# SCH_ocula-mux-bridge-1_1.net
KiCad netlist of a schematic drawn in EasyEDA
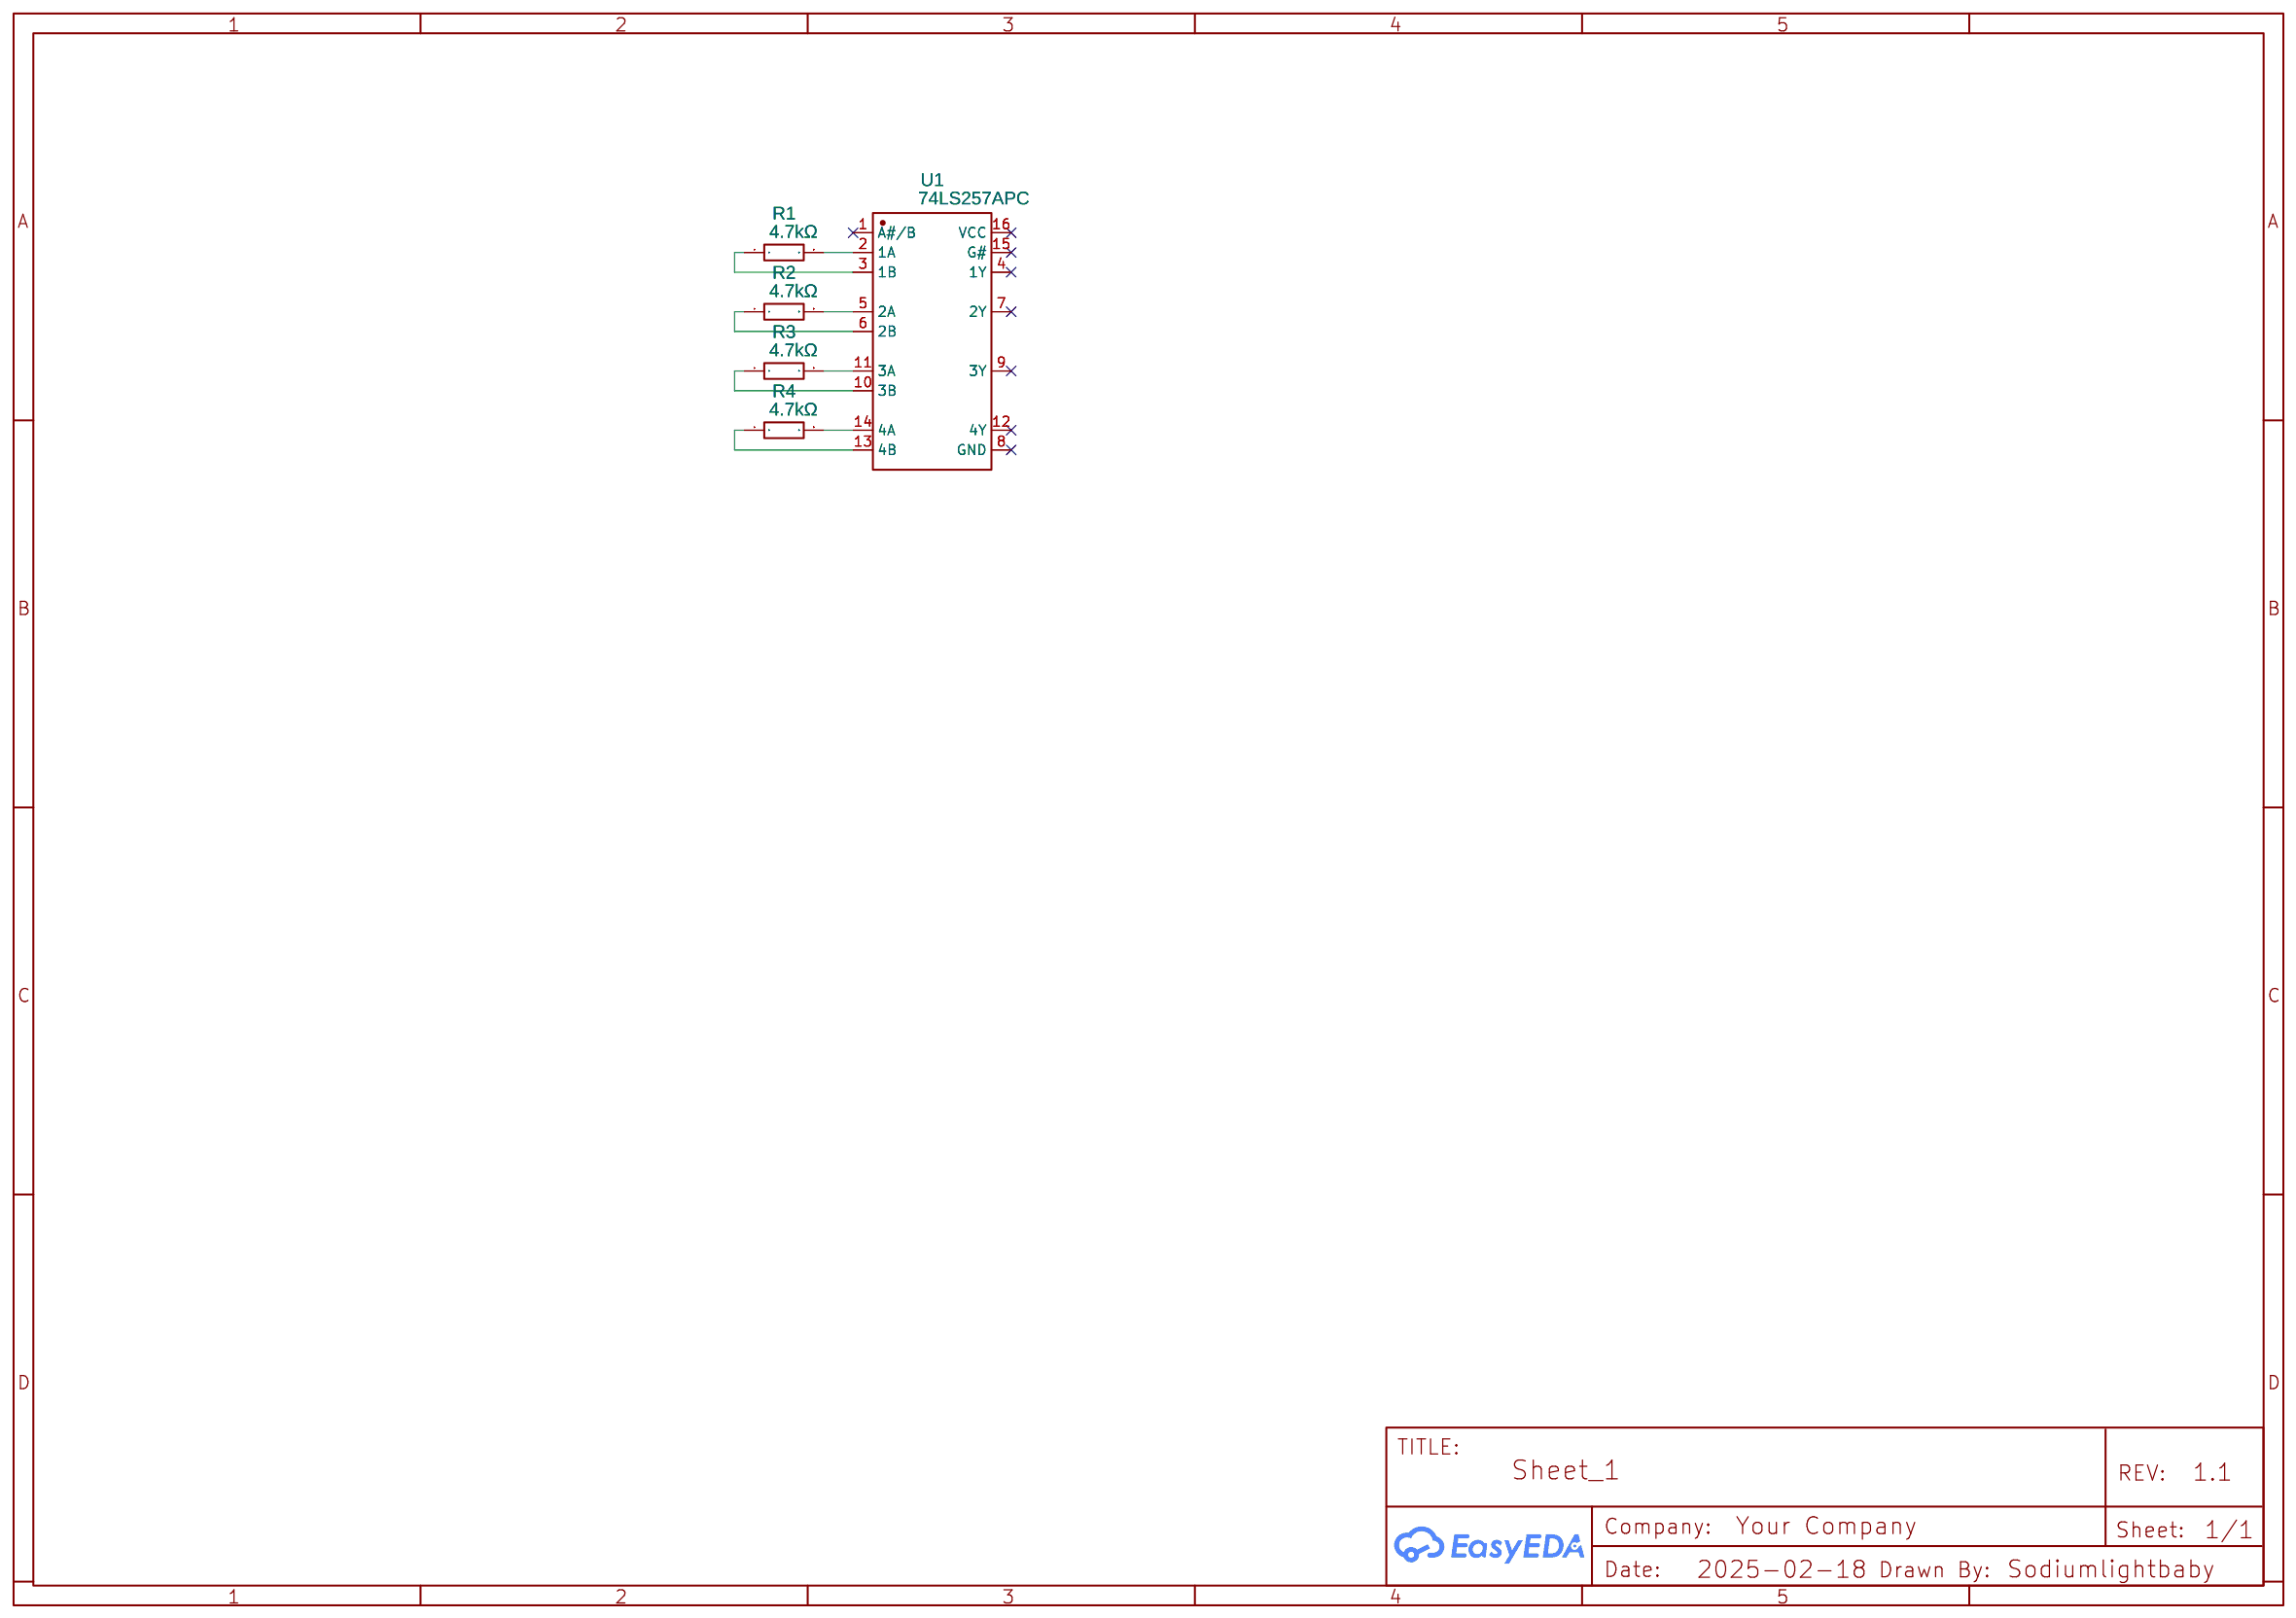
[diagram p0: schematic sheet]

(export (version "E")
  (design (tool "Eeschema 10.0.6"))
  (components
    (comp (ref "R1")
      (value "4.7kΩ")
      (fields
        (field (name "Manufacturer Part") "0805W8F4701T5E")
        (field (name "Manufacturer") "UNI-ROYAL(厚声)")
      )
      (libsource (lib "") (part "0805W8F4701T5E"))
    )
    (comp (ref "R2")
      (value "4.7kΩ")
      (fields
        (field (name "Manufacturer Part") "0805W8F4701T5E")
        (field (name "Manufacturer") "UNI-ROYAL(厚声)")
      )
      (libsource (lib "") (part "0805W8F4701T5E"))
    )
    (comp (ref "R3")
      (value "4.7kΩ")
      (fields
        (field (name "Manufacturer Part") "0805W8F4701T5E")
        (field (name "Manufacturer") "UNI-ROYAL(厚声)")
      )
      (libsource (lib "") (part "0805W8F4701T5E"))
    )
    (comp (ref "R4")
      (value "4.7kΩ")
      (fields
        (field (name "Manufacturer Part") "0805W8F4701T5E")
        (field (name "Manufacturer") "UNI-ROYAL(厚声)")
      )
      (libsource (lib "") (part "0805W8F4701T5E"))
    )
    (comp (ref "U1")
      (value "74LS257APC")
      (fields (field (name "Manufacturer") "TI(德州仪器)"))
      (libsource (lib "") (part "74LS257APC"))
    )
  )
  (nets
    (net (code "1") (name "Net-(U1-1A)") (class "Default")
      (node (ref "R1") (pin "2") (pinfunction "2_2") (pintype "input"))
      (node (ref "U1") (pin "2") (pinfunction "1A_2") (pintype "unspecified"))
    )
    (net (code "2") (name "Net-(U1-1B)") (class "Default")
      (node (ref "R1") (pin "1") (pinfunction "1_1") (pintype "input"))
      (node (ref "U1") (pin "3") (pinfunction "1B_3") (pintype "unspecified"))
    )
    (net (code "3") (name "Net-(U1-2A)") (class "Default")
      (node (ref "R2") (pin "2") (pinfunction "2_2") (pintype "input"))
      (node (ref "U1") (pin "5") (pinfunction "2A_5") (pintype "unspecified"))
    )
    (net (code "4") (name "Net-(U1-2B)") (class "Default")
      (node (ref "R2") (pin "1") (pinfunction "1_1") (pintype "input"))
      (node (ref "U1") (pin "6") (pinfunction "2B_6") (pintype "unspecified"))
    )
    (net (code "5") (name "Net-(U1-3A)") (class "Default")
      (node (ref "R3") (pin "2") (pinfunction "2_2") (pintype "input"))
      (node (ref "U1") (pin "11") (pinfunction "3A_11") (pintype "unspecified"))
    )
    (net (code "6") (name "Net-(U1-3B)") (class "Default")
      (node (ref "R3") (pin "1") (pinfunction "1_1") (pintype "input"))
      (node (ref "U1") (pin "10") (pinfunction "3B_10") (pintype "unspecified"))
    )
    (net (code "7") (name "Net-(U1-4A)") (class "Default")
      (node (ref "R4") (pin "2") (pinfunction "2_2") (pintype "input"))
      (node (ref "U1") (pin "14") (pinfunction "4A_14") (pintype "unspecified"))
    )
    (net (code "8") (name "Net-(U1-4B)") (class "Default")
      (node (ref "R4") (pin "1") (pinfunction "1_1") (pintype "input"))
      (node (ref "U1") (pin "13") (pinfunction "4B_13") (pintype "unspecified"))
    )
    (net (code "9") (name "unconnected-(U1-1Y-Pad4)") (class "Default")
      (node (ref "U1") (pin "4") (pinfunction "1Y_4") (pintype "unspecified+no_connect"))
    )
    (net (code "10") (name "unconnected-(U1-2Y-Pad7)") (class "Default")
      (node (ref "U1") (pin "7") (pinfunction "2Y_7") (pintype "unspecified+no_connect"))
    )
    (net (code "11") (name "unconnected-(U1-3Y-Pad9)") (class "Default")
      (node (ref "U1") (pin "9") (pinfunction "3Y_9") (pintype "unspecified+no_connect"))
    )
    (net (code "12") (name "unconnected-(U1-4Y-Pad12)") (class "Default")
      (node (ref "U1") (pin "12") (pinfunction "4Y_12") (pintype "unspecified+no_connect"))
    )
    (net (code "13") (name "unconnected-(U1-A#{slash}B-Pad1)") (class "Default")
      (node (ref "U1") (pin "1") (pinfunction "A#/B_1") (pintype "unspecified+no_connect"))
    )
    (net (code "14") (name "unconnected-(U1-G#-Pad15)") (class "Default")
      (node (ref "U1") (pin "15") (pinfunction "G#_15") (pintype "unspecified+no_connect"))
    )
    (net (code "15") (name "unconnected-(U1-GND-Pad8)") (class "Default")
      (node (ref "U1") (pin "8") (pinfunction "GND_8") (pintype "unspecified+no_connect"))
    )
    (net (code "16") (name "unconnected-(U1-VCC-Pad16)") (class "Default")
      (node (ref "U1") (pin "16") (pinfunction "VCC_16") (pintype "unspecified+no_connect"))
    )
  )
)
